# 06_-_RAM_DDR2.net
KiCad netlist of a schematic drawn in Altium Designer
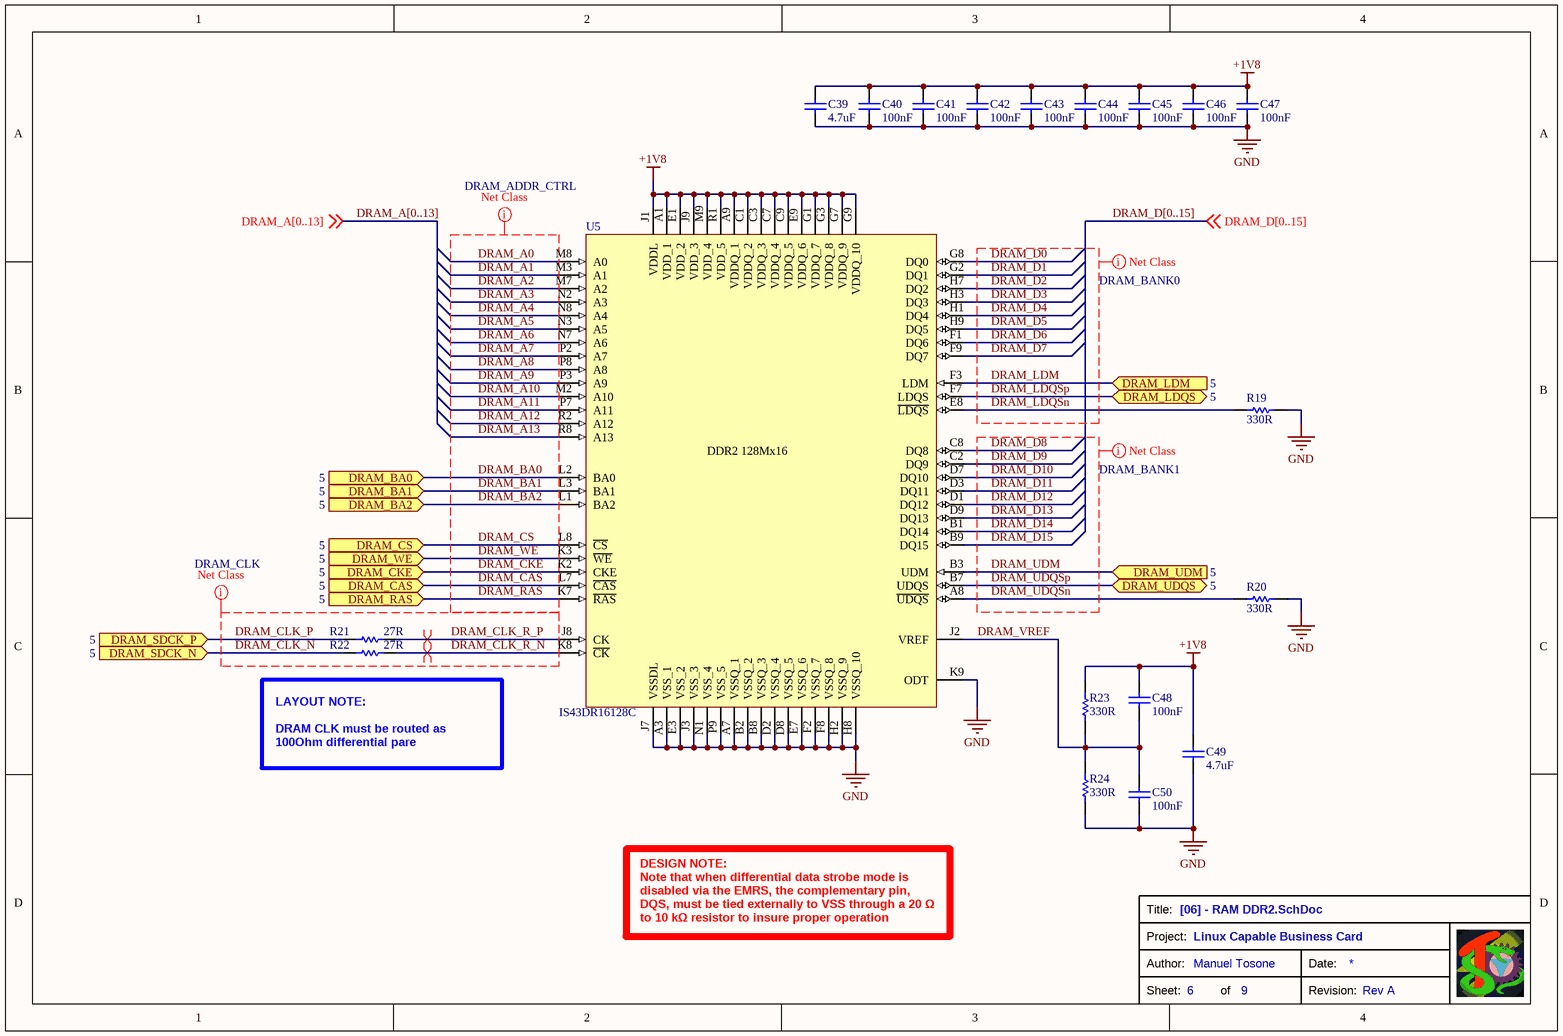
[diagram p0: [06] - RAM DDR2.SchDoc]

(export (version "E")
  (design (tool "Eeschema 10.0.6"))
  (components
    (comp (ref "C39")
      (value "4.7uF")
      (footprint "CAP-0805")
      (description "Multilayer Ceramic Capacitors MLCC - SMD/SMT WCAP-CSGP 4.7uF 0805 20% 16V MLCC")
      (fields (field (name "MANUFACTURER") "Wurth Elektronik") (field (name "Comment") "885012107013"))
      (libsource (lib "Linux-Capable-Business-Card") (part "CAP-0805-4.7u-885012107013_2"))
    )
    (comp (ref "C40")
      (value "100nF")
      (footprint "CAP-0603")
      (description "Multilayer Ceramic Capacitors MLCC - SMD/SMT 16V 0.1uF X7R 0603 20%")
      (fields (field (name "MANUFACTURER") "KEMET") (field (name "Comment") "C0603C104M4RAC"))
      (libsource (lib "Linux-Capable-Business-Card") (part "CAP-0603-100n-C0603C104M4RAC"))
    )
    (comp (ref "C41")
      (value "100nF")
      (footprint "CAP-0603")
      (description "Multilayer Ceramic Capacitors MLCC - SMD/SMT 16V 0.1uF X7R 0603 20%")
      (fields (field (name "MANUFACTURER") "KEMET") (field (name "Comment") "C0603C104M4RAC"))
      (libsource (lib "Linux-Capable-Business-Card") (part "CAP-0603-100n-C0603C104M4RAC"))
    )
    (comp (ref "C42")
      (value "100nF")
      (footprint "CAP-0603")
      (description "Multilayer Ceramic Capacitors MLCC - SMD/SMT 16V 0.1uF X7R 0603 20%")
      (fields (field (name "MANUFACTURER") "KEMET") (field (name "Comment") "C0603C104M4RAC"))
      (libsource (lib "Linux-Capable-Business-Card") (part "CAP-0603-100n-C0603C104M4RAC"))
    )
    (comp (ref "C43")
      (value "100nF")
      (footprint "CAP-0603")
      (description "Multilayer Ceramic Capacitors MLCC - SMD/SMT 16V 0.1uF X7R 0603 20%")
      (fields (field (name "MANUFACTURER") "KEMET") (field (name "Comment") "C0603C104M4RAC"))
      (libsource (lib "Linux-Capable-Business-Card") (part "CAP-0603-100n-C0603C104M4RAC"))
    )
    (comp (ref "C44")
      (value "100nF")
      (footprint "CAP-0603")
      (description "Multilayer Ceramic Capacitors MLCC - SMD/SMT 16V 0.1uF X7R 0603 20%")
      (fields (field (name "MANUFACTURER") "KEMET") (field (name "Comment") "C0603C104M4RAC"))
      (libsource (lib "Linux-Capable-Business-Card") (part "CAP-0603-100n-C0603C104M4RAC"))
    )
    (comp (ref "C45")
      (value "100nF")
      (footprint "CAP-0603")
      (description "Multilayer Ceramic Capacitors MLCC - SMD/SMT 16V 0.1uF X7R 0603 20%")
      (fields (field (name "MANUFACTURER") "KEMET") (field (name "Comment") "C0603C104M4RAC"))
      (libsource (lib "Linux-Capable-Business-Card") (part "CAP-0603-100n-C0603C104M4RAC"))
    )
    (comp (ref "C46")
      (value "100nF")
      (footprint "CAP-0603")
      (description "Multilayer Ceramic Capacitors MLCC - SMD/SMT 16V 0.1uF X7R 0603 20%")
      (fields (field (name "MANUFACTURER") "KEMET") (field (name "Comment") "C0603C104M4RAC"))
      (libsource (lib "Linux-Capable-Business-Card") (part "CAP-0603-100n-C0603C104M4RAC"))
    )
    (comp (ref "C47")
      (value "100nF")
      (footprint "CAP-0603")
      (description "Multilayer Ceramic Capacitors MLCC - SMD/SMT 16V 0.1uF X7R 0603 20%")
      (fields (field (name "MANUFACTURER") "KEMET") (field (name "Comment") "C0603C104M4RAC"))
      (libsource (lib "Linux-Capable-Business-Card") (part "CAP-0603-100n-C0603C104M4RAC"))
    )
    (comp (ref "C48")
      (value "100nF")
      (footprint "CAP-0603")
      (description "Multilayer Ceramic Capacitors MLCC - SMD/SMT 16V 0.1uF X7R 0603 20%")
      (fields (field (name "MANUFACTURER") "KEMET") (field (name "Comment") "C0603C104M4RAC"))
      (libsource (lib "Linux-Capable-Business-Card") (part "CAP-0603-100n-C0603C104M4RAC"))
    )
    (comp (ref "C49")
      (value "4.7uF")
      (footprint "CAP-0805")
      (description "Multilayer Ceramic Capacitors MLCC - SMD/SMT WCAP-CSGP 4.7uF 0805 20% 16V MLCC")
      (fields (field (name "MANUFACTURER") "Wurth Elektronik") (field (name "Comment") "885012107013"))
      (libsource (lib "Linux-Capable-Business-Card") (part "CAP-0805-4.7u-885012107013_2"))
    )
    (comp (ref "C50")
      (value "100nF")
      (footprint "CAP-0603")
      (description "Multilayer Ceramic Capacitors MLCC - SMD/SMT 16V 0.1uF X7R 0603 20%")
      (fields (field (name "MANUFACTURER") "KEMET") (field (name "Comment") "C0603C104M4RAC"))
      (libsource (lib "Linux-Capable-Business-Card") (part "CAP-0603-100n-C0603C104M4RAC"))
    )
    (comp (ref "R19")
      (value "330R")
      (footprint "RES-0603")
      (description "Thin Film Resistors - SMD 1/10W 330 ohm 1% 50ppm")
      (fields (field (name "MANUFACTURER") "Yageo") (field (name "Comment") "RT0603FRD07330RL"))
      (libsource (lib "Linux-Capable-Business-Card") (part "RES-0603-330R-RT0603FRD07330RL"))
    )
    (comp (ref "R20")
      (value "330R")
      (footprint "RES-0603")
      (description "Thin Film Resistors - SMD 1/10W 330 ohm 1% 50ppm")
      (fields (field (name "MANUFACTURER") "Yageo") (field (name "Comment") "RT0603FRD07330RL"))
      (libsource (lib "Linux-Capable-Business-Card") (part "RES-0603-330R-RT0603FRD07330RL"))
    )
    (comp (ref "R21")
      (value "27R")
      (footprint "RES-0603")
      (description "Thin Film Resistors - SMD 1/10W 27 ohm 1% 50ppm")
      (fields (field (name "MANUFACTURER") "Yageo") (field (name "Comment") "RT0603DRD0727RL"))
      (libsource (lib "Linux-Capable-Business-Card") (part "RES-0603-27R-RT0603DRD0727RL"))
    )
    (comp (ref "R22")
      (value "27R")
      (footprint "RES-0603")
      (description "Thin Film Resistors - SMD 1/10W 27 ohm 1% 50ppm")
      (fields (field (name "MANUFACTURER") "Yageo") (field (name "Comment") "RT0603DRD0727RL"))
      (libsource (lib "Linux-Capable-Business-Card") (part "RES-0603-27R-RT0603DRD0727RL"))
    )
    (comp (ref "R23")
      (value "330R")
      (footprint "RES-0603")
      (description "Thin Film Resistors - SMD 1/10W 330 ohm 1% 50ppm")
      (fields (field (name "MANUFACTURER") "Yageo") (field (name "Comment") "RT0603FRD07330RL"))
      (libsource (lib "Linux-Capable-Business-Card") (part "RES-0603-330R-RT0603FRD07330RL"))
    )
    (comp (ref "R24")
      (value "330R")
      (footprint "RES-0603")
      (description "Thin Film Resistors - SMD 1/10W 330 ohm 1% 50ppm")
      (fields (field (name "MANUFACTURER") "Yageo") (field (name "Comment") "RT0603FRD07330RL"))
      (libsource (lib "Linux-Capable-Business-Card") (part "RES-0603-330R-RT0603FRD07330RL"))
    )
    (comp (ref "U5")
      (value "IS43DR16128C")
      (footprint "BGA0.8_DDR2_86_9X12.5")
      (description "256Mx8, 128Mx16 DDR2 DRAM")
      (libsource (lib "Linux-Capable-Business-Card") (part "ISSI-DDR2-IS43DR16128C"))
    )
  )
  (nets
    (net (code "1") (name "+1V8") (class "Default")
      (node (ref "C39") (pin "2") (pinfunction "2_2") (pintype "passive"))
      (node (ref "C40") (pin "2") (pinfunction "2_2") (pintype "passive"))
      (node (ref "C41") (pin "2") (pinfunction "2_2") (pintype "passive"))
      (node (ref "C42") (pin "2") (pinfunction "2_2") (pintype "passive"))
      (node (ref "C43") (pin "2") (pinfunction "2_2") (pintype "passive"))
      (node (ref "C44") (pin "2") (pinfunction "2_2") (pintype "passive"))
      (node (ref "C45") (pin "2") (pinfunction "2_2") (pintype "passive"))
      (node (ref "C46") (pin "2") (pinfunction "2_2") (pintype "passive"))
      (node (ref "C47") (pin "2") (pinfunction "2_2") (pintype "passive"))
      (node (ref "C48") (pin "2") (pinfunction "2_2") (pintype "passive"))
      (node (ref "C49") (pin "2") (pinfunction "2_2") (pintype "passive"))
      (node (ref "R23") (pin "2") (pinfunction "2_2") (pintype "passive"))
      (node (ref "U5") (pin "A1") (pinfunction "VDD_1_A1") (pintype "power_in"))
      (node (ref "U5") (pin "A9") (pinfunction "VDDQ_1_A9") (pintype "power_in"))
      (node (ref "U5") (pin "C1") (pinfunction "VDDQ_2_C1") (pintype "power_in"))
      (node (ref "U5") (pin "C3") (pinfunction "VDDQ_3_C3") (pintype "power_in"))
      (node (ref "U5") (pin "C7") (pinfunction "VDDQ_4_C7") (pintype "power_in"))
      (node (ref "U5") (pin "C9") (pinfunction "VDDQ_5_C9") (pintype "power_in"))
      (node (ref "U5") (pin "E1") (pinfunction "VDD_2_E1") (pintype "power_in"))
      (node (ref "U5") (pin "E9") (pinfunction "VDDQ_6_E9") (pintype "power_in"))
      (node (ref "U5") (pin "G1") (pinfunction "VDDQ_7_G1") (pintype "power_in"))
      (node (ref "U5") (pin "G3") (pinfunction "VDDQ_8_G3") (pintype "power_in"))
      (node (ref "U5") (pin "G7") (pinfunction "VDDQ_9_G7") (pintype "power_in"))
      (node (ref "U5") (pin "G9") (pinfunction "VDDQ_10_G9") (pintype "power_in"))
      (node (ref "U5") (pin "J1") (pinfunction "VDDL_J1") (pintype "power_in"))
      (node (ref "U5") (pin "J9") (pinfunction "VDD_3_J9") (pintype "power_in"))
      (node (ref "U5") (pin "M9") (pinfunction "VDD_4_M9") (pintype "power_in"))
      (node (ref "U5") (pin "R1") (pinfunction "VDD_5_R1") (pintype "power_in"))
    )
    (net (code "2") (name "/DRAM_BA0") (class "Default")
      (node (ref "U5") (pin "L2") (pinfunction "BA0_L2") (pintype "input"))
    )
    (net (code "3") (name "/DRAM_BA1") (class "Default")
      (node (ref "U5") (pin "L3") (pinfunction "BA1_L3") (pintype "input"))
    )
    (net (code "4") (name "/DRAM_BA2") (class "Default")
      (node (ref "U5") (pin "L1") (pinfunction "BA2_L1") (pintype "input"))
    )
    (net (code "5") (name "/DRAM_CAS") (class "Default")
      (node (ref "U5") (pin "L7") (pinfunction "~{CAS}_L7") (pintype "input"))
    )
    (net (code "6") (name "/DRAM_CKE") (class "Default")
      (node (ref "U5") (pin "K2") (pinfunction "CKE_K2") (pintype "input"))
    )
    (net (code "7") (name "/DRAM_CLK_N") (class "Default")
      (node (ref "R22") (pin "1") (pinfunction "1_1") (pintype "passive"))
    )
    (net (code "8") (name "/DRAM_CLK_P") (class "Default")
      (node (ref "R21") (pin "1") (pinfunction "1_1") (pintype "passive"))
    )
    (net (code "9") (name "/DRAM_CLK_R_N") (class "Default")
      (node (ref "R22") (pin "2") (pinfunction "2_2") (pintype "passive"))
      (node (ref "U5") (pin "K8") (pinfunction "~{CK}_K8") (pintype "input"))
    )
    (net (code "10") (name "/DRAM_CLK_R_P") (class "Default")
      (node (ref "R21") (pin "2") (pinfunction "2_2") (pintype "passive"))
      (node (ref "U5") (pin "J8") (pinfunction "CK_J8") (pintype "input"))
    )
    (net (code "11") (name "/DRAM_CS") (class "Default")
      (node (ref "U5") (pin "L8") (pinfunction "~{CS}_L8") (pintype "input"))
    )
    (net (code "12") (name "/DRAM_LDM") (class "Default")
      (node (ref "U5") (pin "F3") (pinfunction "LDM_F3") (pintype "input"))
    )
    (net (code "13") (name "/DRAM_LDQSn") (class "Default")
      (node (ref "R19") (pin "2") (pinfunction "2_2") (pintype "passive"))
      (node (ref "U5") (pin "E8") (pinfunction "~{LDQS}_E8") (pintype "bidirectional"))
    )
    (net (code "14") (name "/DRAM_LDQSp") (class "Default")
      (node (ref "U5") (pin "F7") (pinfunction "LDQS_F7") (pintype "bidirectional"))
    )
    (net (code "15") (name "/DRAM_RAS") (class "Default")
      (node (ref "U5") (pin "K7") (pinfunction "~{RAS}_K7") (pintype "input"))
    )
    (net (code "16") (name "/DRAM_UDM") (class "Default")
      (node (ref "U5") (pin "B3") (pinfunction "UDM_B3") (pintype "input"))
    )
    (net (code "17") (name "/DRAM_UDQSn") (class "Default")
      (node (ref "R20") (pin "2") (pinfunction "2_2") (pintype "passive"))
      (node (ref "U5") (pin "A8") (pinfunction "~{UDQS}_A8") (pintype "bidirectional"))
    )
    (net (code "18") (name "/DRAM_UDQSp") (class "Default")
      (node (ref "U5") (pin "B7") (pinfunction "UDQS_B7") (pintype "bidirectional"))
    )
    (net (code "19") (name "/DRAM_VREF") (class "Default")
      (node (ref "C48") (pin "1") (pinfunction "1_1") (pintype "passive"))
      (node (ref "C50") (pin "2") (pinfunction "2_2") (pintype "passive"))
      (node (ref "R23") (pin "1") (pinfunction "1_1") (pintype "passive"))
      (node (ref "R24") (pin "2") (pinfunction "2_2") (pintype "passive"))
      (node (ref "U5") (pin "J2") (pinfunction "VREF_J2") (pintype "passive"))
    )
    (net (code "20") (name "/DRAM_WE") (class "Default")
      (node (ref "U5") (pin "K3") (pinfunction "~{WE}_K3") (pintype "input"))
    )
    (net (code "21") (name "DRAM_A0") (class "Default")
      (node (ref "U5") (pin "M8") (pinfunction "A0_M8") (pintype "input"))
    )
    (net (code "22") (name "DRAM_A1") (class "Default")
      (node (ref "U5") (pin "M3") (pinfunction "A1_M3") (pintype "input"))
    )
    (net (code "23") (name "DRAM_A2") (class "Default")
      (node (ref "U5") (pin "M7") (pinfunction "A2_M7") (pintype "input"))
    )
    (net (code "24") (name "DRAM_A3") (class "Default")
      (node (ref "U5") (pin "N2") (pinfunction "A3_N2") (pintype "input"))
    )
    (net (code "25") (name "DRAM_A4") (class "Default")
      (node (ref "U5") (pin "N8") (pinfunction "A4_N8") (pintype "input"))
    )
    (net (code "26") (name "DRAM_A5") (class "Default")
      (node (ref "U5") (pin "N3") (pinfunction "A5_N3") (pintype "input"))
    )
    (net (code "27") (name "DRAM_A6") (class "Default")
      (node (ref "U5") (pin "N7") (pinfunction "A6_N7") (pintype "input"))
    )
    (net (code "28") (name "DRAM_A7") (class "Default")
      (node (ref "U5") (pin "P2") (pinfunction "A7_P2") (pintype "input"))
    )
    (net (code "29") (name "DRAM_A8") (class "Default")
      (node (ref "U5") (pin "P8") (pinfunction "A8_P8") (pintype "input"))
    )
    (net (code "30") (name "DRAM_A9") (class "Default")
      (node (ref "U5") (pin "P3") (pinfunction "A9_P3") (pintype "input"))
    )
    (net (code "31") (name "DRAM_A10") (class "Default")
      (node (ref "U5") (pin "M2") (pinfunction "A10_M2") (pintype "input"))
    )
    (net (code "32") (name "DRAM_A11") (class "Default")
      (node (ref "U5") (pin "P7") (pinfunction "A11_P7") (pintype "input"))
    )
    (net (code "33") (name "DRAM_A12") (class "Default")
      (node (ref "U5") (pin "R2") (pinfunction "A12_R2") (pintype "input"))
    )
    (net (code "34") (name "DRAM_A13") (class "Default")
      (node (ref "U5") (pin "R8") (pinfunction "A13_R8") (pintype "input"))
    )
    (net (code "36") (name "DRAM_D0") (class "Default")
      (node (ref "U5") (pin "G8") (pinfunction "DQ0_G8") (pintype "bidirectional"))
    )
    (net (code "37") (name "DRAM_D1") (class "Default")
      (node (ref "U5") (pin "G2") (pinfunction "DQ1_G2") (pintype "bidirectional"))
    )
    (net (code "38") (name "DRAM_D2") (class "Default")
      (node (ref "U5") (pin "H7") (pinfunction "DQ2_H7") (pintype "bidirectional"))
    )
    (net (code "39") (name "DRAM_D3") (class "Default")
      (node (ref "U5") (pin "H3") (pinfunction "DQ3_H3") (pintype "bidirectional"))
    )
    (net (code "40") (name "DRAM_D4") (class "Default")
      (node (ref "U5") (pin "H1") (pinfunction "DQ4_H1") (pintype "bidirectional"))
    )
    (net (code "41") (name "DRAM_D5") (class "Default")
      (node (ref "U5") (pin "H9") (pinfunction "DQ5_H9") (pintype "bidirectional"))
    )
    (net (code "42") (name "DRAM_D6") (class "Default")
      (node (ref "U5") (pin "F1") (pinfunction "DQ6_F1") (pintype "bidirectional"))
    )
    (net (code "43") (name "DRAM_D7") (class "Default")
      (node (ref "U5") (pin "F9") (pinfunction "DQ7_F9") (pintype "bidirectional"))
    )
    (net (code "44") (name "DRAM_D8") (class "Default")
      (node (ref "U5") (pin "C8") (pinfunction "DQ8_C8") (pintype "bidirectional"))
    )
    (net (code "45") (name "DRAM_D9") (class "Default")
      (node (ref "U5") (pin "C2") (pinfunction "DQ9_C2") (pintype "bidirectional"))
    )
    (net (code "46") (name "DRAM_D10") (class "Default")
      (node (ref "U5") (pin "D7") (pinfunction "DQ10_D7") (pintype "bidirectional"))
    )
    (net (code "47") (name "DRAM_D11") (class "Default")
      (node (ref "U5") (pin "D3") (pinfunction "DQ11_D3") (pintype "bidirectional"))
    )
    (net (code "48") (name "DRAM_D12") (class "Default")
      (node (ref "U5") (pin "D1") (pinfunction "DQ12_D1") (pintype "bidirectional"))
    )
    (net (code "49") (name "DRAM_D13") (class "Default")
      (node (ref "U5") (pin "D9") (pinfunction "DQ13_D9") (pintype "bidirectional"))
    )
    (net (code "50") (name "DRAM_D14") (class "Default")
      (node (ref "U5") (pin "B1") (pinfunction "DQ14_B1") (pintype "bidirectional"))
    )
    (net (code "51") (name "DRAM_D15") (class "Default")
      (node (ref "U5") (pin "B9") (pinfunction "DQ15_B9") (pintype "bidirectional"))
    )
    (net (code "53") (name "GND") (class "Default")
      (node (ref "C39") (pin "1") (pinfunction "1_1") (pintype "passive"))
      (node (ref "C40") (pin "1") (pinfunction "1_1") (pintype "passive"))
      (node (ref "C41") (pin "1") (pinfunction "1_1") (pintype "passive"))
      (node (ref "C42") (pin "1") (pinfunction "1_1") (pintype "passive"))
      (node (ref "C43") (pin "1") (pinfunction "1_1") (pintype "passive"))
      (node (ref "C44") (pin "1") (pinfunction "1_1") (pintype "passive"))
      (node (ref "C45") (pin "1") (pinfunction "1_1") (pintype "passive"))
      (node (ref "C46") (pin "1") (pinfunction "1_1") (pintype "passive"))
      (node (ref "C47") (pin "1") (pinfunction "1_1") (pintype "passive"))
      (node (ref "C49") (pin "1") (pinfunction "1_1") (pintype "passive"))
      (node (ref "C50") (pin "1") (pinfunction "1_1") (pintype "passive"))
      (node (ref "R19") (pin "1") (pinfunction "1_1") (pintype "passive"))
      (node (ref "R20") (pin "1") (pinfunction "1_1") (pintype "passive"))
      (node (ref "R24") (pin "1") (pinfunction "1_1") (pintype "passive"))
      (node (ref "U5") (pin "A3") (pinfunction "VSS_1_A3") (pintype "power_in"))
      (node (ref "U5") (pin "A7") (pinfunction "VSSQ_1_A7") (pintype "power_in"))
      (node (ref "U5") (pin "B2") (pinfunction "VSSQ_2_B2") (pintype "power_in"))
      (node (ref "U5") (pin "B8") (pinfunction "VSSQ_3_B8") (pintype "power_in"))
      (node (ref "U5") (pin "D2") (pinfunction "VSSQ_4_D2") (pintype "power_in"))
      (node (ref "U5") (pin "D8") (pinfunction "VSSQ_5_D8") (pintype "power_in"))
      (node (ref "U5") (pin "E3") (pinfunction "VSS_2_E3") (pintype "power_in"))
      (node (ref "U5") (pin "E7") (pinfunction "VSSQ_6_E7") (pintype "power_in"))
      (node (ref "U5") (pin "F2") (pinfunction "VSSQ_7_F2") (pintype "power_in"))
      (node (ref "U5") (pin "F8") (pinfunction "VSSQ_8_F8") (pintype "power_in"))
      (node (ref "U5") (pin "H2") (pinfunction "VSSQ_9_H2") (pintype "power_in"))
      (node (ref "U5") (pin "H8") (pinfunction "VSSQ_10_H8") (pintype "power_in"))
      (node (ref "U5") (pin "J3") (pinfunction "VSS_3_J3") (pintype "power_in"))
      (node (ref "U5") (pin "J7") (pinfunction "VSSDL_J7") (pintype "power_in"))
      (node (ref "U5") (pin "K9") (pinfunction "ODT_K9") (pintype "passive"))
      (node (ref "U5") (pin "N1") (pinfunction "VSS_4_N1") (pintype "power_in"))
      (node (ref "U5") (pin "P9") (pinfunction "VSS_5_P9") (pintype "power_in"))
    )
  )
)
